# Screen.net
KiCad netlist of a schematic drawn in Altium Designer
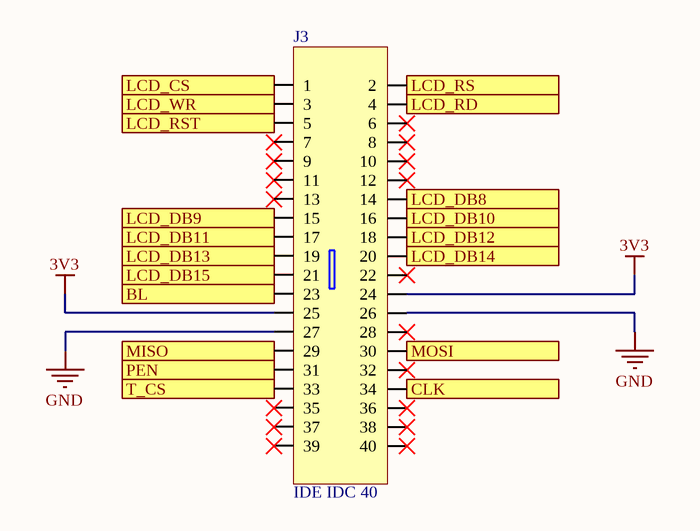
[diagram p0: Screen.SchDoc]

(export (version "E")
  (design (tool "Eeschema 10.0.6"))
  (components
    (comp (ref "J3")
      (value "IDE IDC 40")
      (footprint "IDE 20X2")
      (libsource (lib "My Library") (part "IDC 20X2"))
    )
  )
  (nets
    (net (code "1") (name "/BL") (class "Default")
      (node (ref "J3") (pin "23") (pinfunction "23_23") (pintype "passive"))
    )
    (net (code "2") (name "/CLK") (class "Default")
      (node (ref "J3") (pin "34") (pinfunction "34_34") (pintype "passive"))
    )
    (net (code "3") (name "/LCD_CS") (class "Default")
      (node (ref "J3") (pin "1") (pinfunction "1_1") (pintype "passive"))
    )
    (net (code "4") (name "/LCD_DB8") (class "Default")
      (node (ref "J3") (pin "14") (pinfunction "14_14") (pintype "passive"))
    )
    (net (code "5") (name "/LCD_DB9") (class "Default")
      (node (ref "J3") (pin "15") (pinfunction "15_15") (pintype "passive"))
    )
    (net (code "6") (name "/LCD_DB10") (class "Default")
      (node (ref "J3") (pin "16") (pinfunction "16_16") (pintype "passive"))
    )
    (net (code "7") (name "/LCD_DB11") (class "Default")
      (node (ref "J3") (pin "17") (pinfunction "17_17") (pintype "passive"))
    )
    (net (code "8") (name "/LCD_DB12") (class "Default")
      (node (ref "J3") (pin "18") (pinfunction "18_18") (pintype "passive"))
    )
    (net (code "9") (name "/LCD_DB13") (class "Default")
      (node (ref "J3") (pin "19") (pinfunction "19_19") (pintype "passive"))
    )
    (net (code "10") (name "/LCD_DB14") (class "Default")
      (node (ref "J3") (pin "20") (pinfunction "20_20") (pintype "passive"))
    )
    (net (code "11") (name "/LCD_DB15") (class "Default")
      (node (ref "J3") (pin "21") (pinfunction "21_21") (pintype "passive"))
    )
    (net (code "12") (name "/LCD_RD") (class "Default")
      (node (ref "J3") (pin "4") (pinfunction "4_4") (pintype "passive"))
    )
    (net (code "13") (name "/LCD_RS") (class "Default")
      (node (ref "J3") (pin "2") (pinfunction "2_2") (pintype "passive"))
    )
    (net (code "14") (name "/LCD_RST") (class "Default")
      (node (ref "J3") (pin "5") (pinfunction "5_5") (pintype "passive"))
    )
    (net (code "15") (name "/LCD_WR") (class "Default")
      (node (ref "J3") (pin "3") (pinfunction "3_3") (pintype "passive"))
    )
    (net (code "16") (name "/MISO") (class "Default")
      (node (ref "J3") (pin "29") (pinfunction "29_29") (pintype "passive"))
    )
    (net (code "17") (name "/MOSI") (class "Default")
      (node (ref "J3") (pin "30") (pinfunction "30_30") (pintype "passive"))
    )
    (net (code "18") (name "/PEN") (class "Default")
      (node (ref "J3") (pin "31") (pinfunction "31_31") (pintype "passive"))
    )
    (net (code "19") (name "/T_CS") (class "Default")
      (node (ref "J3") (pin "33") (pinfunction "33_33") (pintype "passive"))
    )
    (net (code "20") (name "3V3") (class "Default")
      (node (ref "J3") (pin "24") (pinfunction "24_24") (pintype "passive"))
      (node (ref "J3") (pin "25") (pinfunction "25_25") (pintype "passive"))
    )
    (net (code "21") (name "GND") (class "Default")
      (node (ref "J3") (pin "26") (pinfunction "26_26") (pintype "passive"))
      (node (ref "J3") (pin "27") (pinfunction "27_27") (pintype "passive"))
    )
    (net (code "22") (name "unconnected-(J3-Pad6)") (class "Default")
      (node (ref "J3") (pin "6") (pinfunction "6_6") (pintype "passive+no_connect"))
    )
    (net (code "23") (name "unconnected-(J3-Pad7)") (class "Default")
      (node (ref "J3") (pin "7") (pinfunction "7_7") (pintype "passive+no_connect"))
    )
    (net (code "24") (name "unconnected-(J3-Pad8)") (class "Default")
      (node (ref "J3") (pin "8") (pinfunction "8_8") (pintype "passive+no_connect"))
    )
    (net (code "25") (name "unconnected-(J3-Pad9)") (class "Default")
      (node (ref "J3") (pin "9") (pinfunction "9_9") (pintype "passive+no_connect"))
    )
    (net (code "26") (name "unconnected-(J3-Pad10)") (class "Default")
      (node (ref "J3") (pin "10") (pinfunction "10_10") (pintype "passive+no_connect"))
    )
    (net (code "27") (name "unconnected-(J3-Pad11)") (class "Default")
      (node (ref "J3") (pin "11") (pinfunction "11_11") (pintype "passive+no_connect"))
    )
    (net (code "28") (name "unconnected-(J3-Pad12)") (class "Default")
      (node (ref "J3") (pin "12") (pinfunction "12_12") (pintype "passive+no_connect"))
    )
    (net (code "29") (name "unconnected-(J3-Pad13)") (class "Default")
      (node (ref "J3") (pin "13") (pinfunction "13_13") (pintype "passive+no_connect"))
    )
    (net (code "30") (name "unconnected-(J3-Pad22)") (class "Default")
      (node (ref "J3") (pin "22") (pinfunction "22_22") (pintype "passive+no_connect"))
    )
    (net (code "31") (name "unconnected-(J3-Pad28)") (class "Default")
      (node (ref "J3") (pin "28") (pinfunction "28_28") (pintype "passive+no_connect"))
    )
    (net (code "32") (name "unconnected-(J3-Pad32)") (class "Default")
      (node (ref "J3") (pin "32") (pinfunction "32_32") (pintype "passive+no_connect"))
    )
    (net (code "33") (name "unconnected-(J3-Pad35)") (class "Default")
      (node (ref "J3") (pin "35") (pinfunction "35_35") (pintype "passive+no_connect"))
    )
    (net (code "34") (name "unconnected-(J3-Pad36)") (class "Default")
      (node (ref "J3") (pin "36") (pinfunction "36_36") (pintype "passive+no_connect"))
    )
    (net (code "35") (name "unconnected-(J3-Pad37)") (class "Default")
      (node (ref "J3") (pin "37") (pinfunction "37_37") (pintype "passive+no_connect"))
    )
    (net (code "36") (name "unconnected-(J3-Pad38)") (class "Default")
      (node (ref "J3") (pin "38") (pinfunction "38_38") (pintype "passive+no_connect"))
    )
    (net (code "37") (name "unconnected-(J3-Pad39)") (class "Default")
      (node (ref "J3") (pin "39") (pinfunction "39_39") (pintype "passive+no_connect"))
    )
    (net (code "38") (name "unconnected-(J3-Pad40)") (class "Default")
      (node (ref "J3") (pin "40") (pinfunction "40_40") (pintype "passive+no_connect"))
    )
  )
)
